# Power.net
KiCad netlist of a schematic drawn in Altium Designer
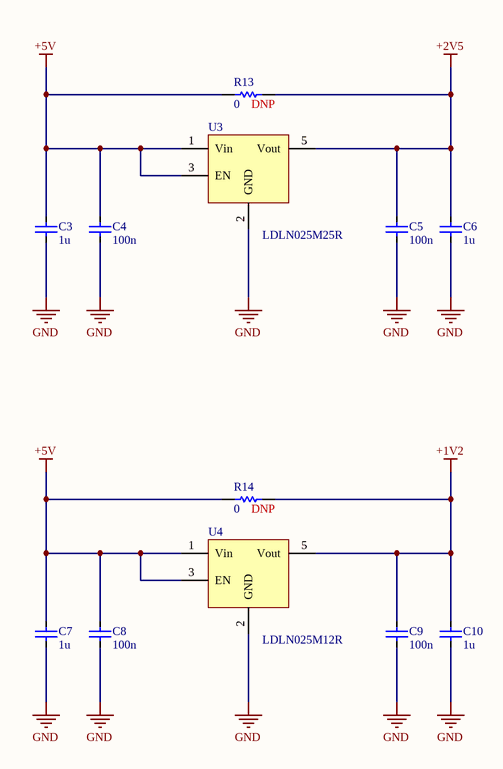
[diagram p0: Power.SchDoc]

(export (version "E")
  (design (tool "Eeschema 10.0.6"))
  (components
    (comp (ref "C3") (value "1u") (footprint "CAP_0402") (libsource (lib "IIS-Lib_TW") (part "Cap")))
    (comp (ref "C4") (value "100n") (footprint "CAP_0402") (libsource (lib "IIS-Lib_TW") (part "Cap")))
    (comp (ref "C5") (value "100n") (footprint "CAP_0402") (libsource (lib "IIS-Lib_TW") (part "Cap")))
    (comp (ref "C6") (value "1u") (footprint "CAP_0402") (libsource (lib "IIS-Lib_TW") (part "Cap")))
    (comp (ref "C7") (value "1u") (footprint "CAP_0402") (libsource (lib "IIS-Lib_TW") (part "Cap")))
    (comp (ref "C8") (value "100n") (footprint "CAP_0402") (libsource (lib "IIS-Lib_TW") (part "Cap")))
    (comp (ref "C9") (value "100n") (footprint "CAP_0402") (libsource (lib "IIS-Lib_TW") (part "Cap")))
    (comp (ref "C10") (value "1u") (footprint "CAP_0402") (libsource (lib "IIS-Lib_TW") (part "Cap")))
    (comp (ref "R13")
      (value "0")
      (footprint "RES_0402")
      (fields (field (name "NOTE") "DNP"))
      (libsource (lib "IIS-Lib_TW") (part "Res"))
    )
    (comp (ref "R14")
      (value "0")
      (footprint "RES_0402")
      (fields (field (name "NOTE") "DNP"))
      (libsource (lib "IIS-Lib_TW") (part "Res"))
    )
    (comp (ref "U3")
      (value "LDLN025M25R")
      (footprint "SOT23-95P280X145-5N")
      (libsource (lib "IIS-Lib_TW") (part "LDLN025MxxR"))
    )
    (comp (ref "U4")
      (value "LDLN025M12R")
      (footprint "SOT23-95P280X145-5N")
      (libsource (lib "IIS-Lib_TW") (part "LDLN025MxxR"))
    )
  )
  (nets
    (net (code "1") (name "+1V2") (class "Default")
      (node (ref "C10") (pin "1") (pinfunction "1_1") (pintype "passive"))
      (node (ref "C9") (pin "1") (pinfunction "1_1") (pintype "passive"))
      (node (ref "R14") (pin "2") (pinfunction "2_2") (pintype "passive"))
      (node (ref "U4") (pin "5") (pinfunction "Vout_5") (pintype "passive"))
    )
    (net (code "2") (name "+2V5") (class "Default")
      (node (ref "C5") (pin "1") (pinfunction "1_1") (pintype "passive"))
      (node (ref "C6") (pin "1") (pinfunction "1_1") (pintype "passive"))
      (node (ref "R13") (pin "2") (pinfunction "2_2") (pintype "passive"))
      (node (ref "U3") (pin "5") (pinfunction "Vout_5") (pintype "passive"))
    )
    (net (code "3") (name "+5V") (class "Default")
      (node (ref "C3") (pin "1") (pinfunction "1_1") (pintype "passive"))
      (node (ref "C4") (pin "1") (pinfunction "1_1") (pintype "passive"))
      (node (ref "C7") (pin "1") (pinfunction "1_1") (pintype "passive"))
      (node (ref "C8") (pin "1") (pinfunction "1_1") (pintype "passive"))
      (node (ref "R13") (pin "1") (pinfunction "1_1") (pintype "passive"))
      (node (ref "R14") (pin "1") (pinfunction "1_1") (pintype "passive"))
      (node (ref "U3") (pin "1") (pinfunction "Vin_1") (pintype "passive"))
      (node (ref "U3") (pin "3") (pinfunction "EN_3") (pintype "passive"))
      (node (ref "U4") (pin "1") (pinfunction "Vin_1") (pintype "passive"))
      (node (ref "U4") (pin "3") (pinfunction "EN_3") (pintype "passive"))
    )
    (net (code "4") (name "GND") (class "Default")
      (node (ref "C10") (pin "2") (pinfunction "2_2") (pintype "passive"))
      (node (ref "C3") (pin "2") (pinfunction "2_2") (pintype "passive"))
      (node (ref "C4") (pin "2") (pinfunction "2_2") (pintype "passive"))
      (node (ref "C5") (pin "2") (pinfunction "2_2") (pintype "passive"))
      (node (ref "C6") (pin "2") (pinfunction "2_2") (pintype "passive"))
      (node (ref "C7") (pin "2") (pinfunction "2_2") (pintype "passive"))
      (node (ref "C8") (pin "2") (pinfunction "2_2") (pintype "passive"))
      (node (ref "C9") (pin "2") (pinfunction "2_2") (pintype "passive"))
      (node (ref "U3") (pin "2") (pinfunction "GND_2") (pintype "passive"))
      (node (ref "U4") (pin "2") (pinfunction "GND_2") (pintype "passive"))
    )
  )
)
